# EchidnaBlack_0.net
KiCad netlist of a schematic drawn in EAGLE
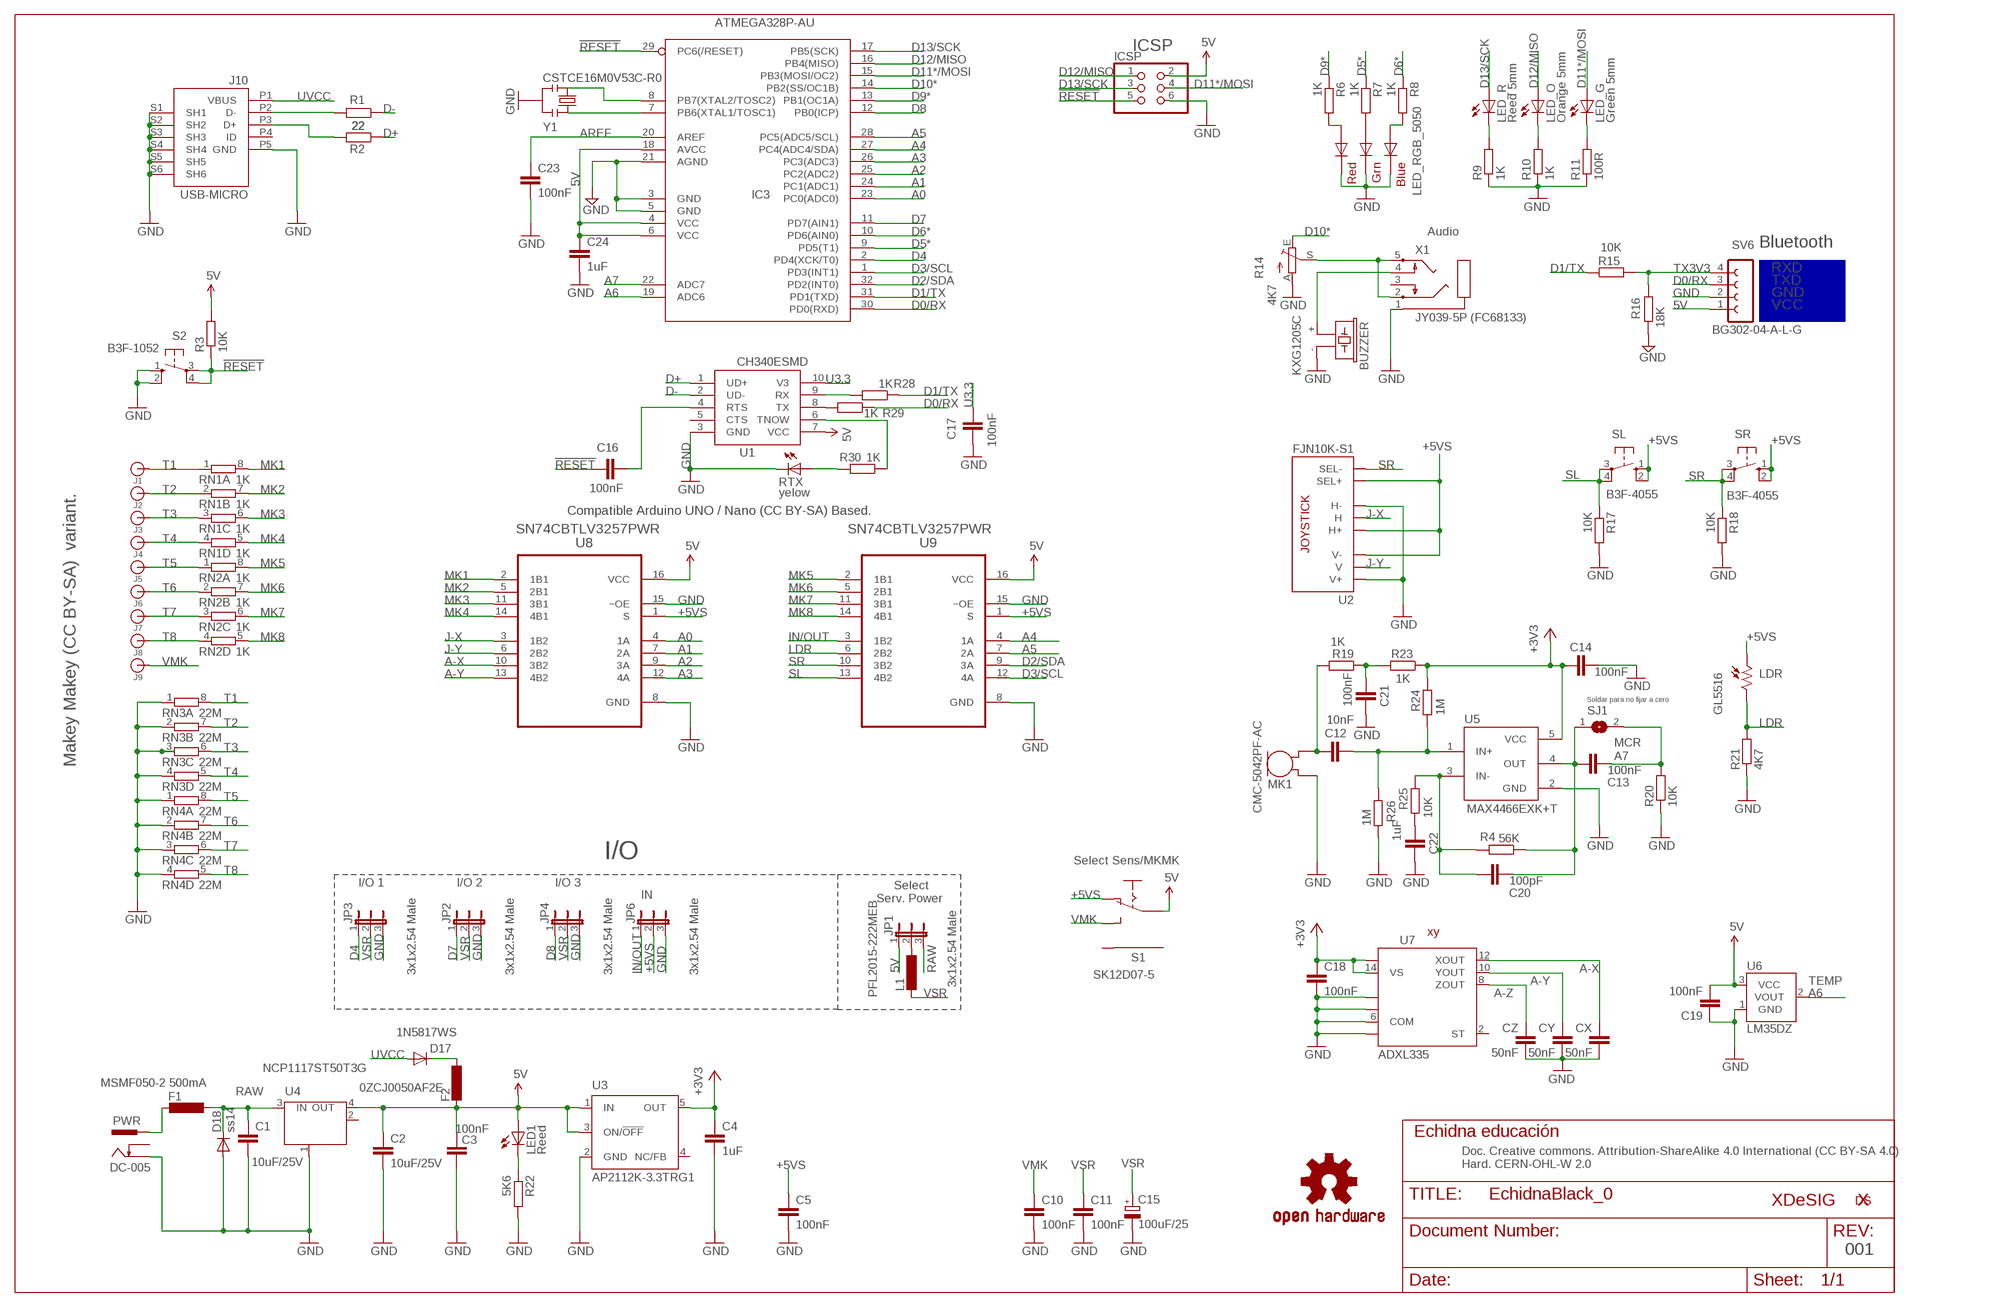
[diagram p0: schematic, sheet 1]

(export (version "E")
  (design (tool "Eeschema 10.0.6"))
  (components
    (comp (ref "BUZZER")
      (value "KXG1205C")
      (footprint "eagle-import:F_CM12P")
      (libsource (lib "eagle-import") (part "F/CM12P"))
    )
    (comp (ref "C1")
      (value "10uF/25V")
      (footprint "eagle-import:C1210")
      (libsource (lib "eagle-import") (part "C-EUC1210"))
    )
    (comp (ref "C2")
      (value "10uF/25V")
      (footprint "eagle-import:C1210")
      (libsource (lib "eagle-import") (part "C-EUC1210"))
    )
    (comp (ref "C3")
      (value "100nF")
      (footprint "eagle-import:0603-CAP")
      (libsource (lib "eagle-import") (part "CAP0603-CAP"))
    )
    (comp (ref "C4")
      (value "1uF")
      (footprint "eagle-import:0603-CAP")
      (libsource (lib "eagle-import") (part "CAP0603-CAP"))
    )
    (comp (ref "C5")
      (value "100nF")
      (footprint "eagle-import:C0603K")
      (libsource (lib "eagle-import") (part "C-EUC0603K"))
    )
    (comp (ref "C10")
      (value "100nF")
      (footprint "eagle-import:C0603K")
      (libsource (lib "eagle-import") (part "C-EUC0603K"))
    )
    (comp (ref "C11")
      (value "100nF")
      (footprint "eagle-import:C0603K")
      (libsource (lib "eagle-import") (part "C-EUC0603K"))
    )
    (comp (ref "C12")
      (value "10nF")
      (footprint "eagle-import:C0603K")
      (libsource (lib "eagle-import") (part "C-EUC0603K"))
    )
    (comp (ref "C13")
      (value "100nF")
      (footprint "eagle-import:C0603K")
      (libsource (lib "eagle-import") (part "C-EUC0603K"))
    )
    (comp (ref "C14")
      (value "100nF")
      (footprint "eagle-import:C0603K")
      (libsource (lib "eagle-import") (part "C-EUC0603K"))
    )
    (comp (ref "C15")
      (value "100uF/25")
      (footprint "eagle-import:PANASONIC_D")
      (libsource (lib "eagle-import") (part "CPOL-EUD"))
    )
    (comp (ref "C16")
      (value "100nF")
      (footprint "eagle-import:C0603-ROUND")
      (fields (field (name "PART_NUMBER") "cl10b104kbnc"))
      (libsource (lib "eagle-import") (part "0015_100NF_0603"))
    )
    (comp (ref "C17")
      (value "100nF")
      (footprint "eagle-import:C0603-ROUND")
      (fields (field (name "PART_NUMBER") "cl10b104kbnc"))
      (libsource (lib "eagle-import") (part "0015_100NF_0603"))
    )
    (comp (ref "C18")
      (value "100nF")
      (footprint "eagle-import:C0603K")
      (libsource (lib "eagle-import") (part "C-EUC0603K"))
    )
    (comp (ref "C19")
      (value "100nF")
      (footprint "eagle-import:C0603K")
      (libsource (lib "eagle-import") (part "C-EUC0603K"))
    )
    (comp (ref "C20")
      (value "100pF")
      (footprint "eagle-import:C0603K")
      (libsource (lib "eagle-import") (part "C-EUC0603K"))
    )
    (comp (ref "C21")
      (value "100nF")
      (footprint "eagle-import:C0603K")
      (libsource (lib "eagle-import") (part "C-EUC0603K"))
    )
    (comp (ref "C22")
      (value "1uF")
      (footprint "eagle-import:C0603K")
      (libsource (lib "eagle-import") (part "C-EUC0603K"))
    )
    (comp (ref "C23")
      (value "100nF")
      (footprint "eagle-import:C0603-ROUND")
      (fields (field (name "PART_NUMBER") "cl10b104kbnc"))
      (libsource (lib "eagle-import") (part "0015_100NF_0603"))
    )
    (comp (ref "C24")
      (value "1uF")
      (footprint "eagle-import:C0603-ROUND")
      (fields (field (name "PART_NUMBER") "1uF_0603/GRM188R61E105KA12D"))
      (libsource (lib "eagle-import") (part "0006_1UF_0603/GRM188R61E105KA12D"))
    )
    (comp (ref "CX")
      (value "50nF")
      (footprint "eagle-import:C0603K")
      (libsource (lib "eagle-import") (part "C-EUC0603K"))
    )
    (comp (ref "CY")
      (value "50nF")
      (footprint "eagle-import:C0603K")
      (libsource (lib "eagle-import") (part "C-EUC0603K"))
    )
    (comp (ref "CZ")
      (value "50nF")
      (footprint "eagle-import:C0603K")
      (libsource (lib "eagle-import") (part "C-EUC0603K"))
    )
    (comp (ref "D17")
      (value "1N5817WS")
      (footprint "eagle-import:SOD-323")
      (libsource (lib "eagle-import") (part "DIODESOD"))
    )
    (comp (ref "D18")
      (value "ss14")
      (footprint "eagle-import:DO214AC")
      (libsource (lib "eagle-import") (part "DIODE-DO214AC"))
    )
    (comp (ref "F1")
      (value "MSMF050-2 500mA")
      (footprint "eagle-import:L1812")
      (libsource (lib "eagle-import") (part "L-EUL1812"))
    )
    (comp (ref "F2")
      (value "0ZCJ0050AF2E")
      (footprint "eagle-import:L3216C")
      (libsource (lib "eagle-import") (part "L-EUL3216C"))
    )
    (comp (ref "IC3")
      (value "ATMEGA328P-AU")
      (footprint "eagle-import:TQFP32-08")
      (libsource (lib "eagle-import") (part "0265_ATMEGA328P-AU"))
    )
    (comp (ref "ICSP")
      (value "0114_PH254-203DF118A00V")
      (footprint "eagle-import:2X03")
      (fields (field (name "PART_NUMBER") "PH254-203DF118A00V"))
      (libsource (lib "eagle-import") (part "0114_PH254-203DF118A00V"))
    )
    (comp (ref "J1")
      (value "Hole")
      (footprint "eagle-import:BANANA_CONN")
      (libsource (lib "eagle-import") (part "BANANA_CONN"))
    )
    (comp (ref "J2")
      (value "Hole")
      (footprint "eagle-import:BANANA_CONN")
      (libsource (lib "eagle-import") (part "BANANA_CONN"))
    )
    (comp (ref "J3")
      (value "Hole")
      (footprint "eagle-import:BANANA_CONN")
      (libsource (lib "eagle-import") (part "BANANA_CONN"))
    )
    (comp (ref "J4")
      (value "Hole")
      (footprint "eagle-import:BANANA_CONN")
      (libsource (lib "eagle-import") (part "BANANA_CONN"))
    )
    (comp (ref "J5")
      (value "Hole")
      (footprint "eagle-import:BANANA_CONN")
      (libsource (lib "eagle-import") (part "BANANA_CONN"))
    )
    (comp (ref "J6")
      (value "Hole")
      (footprint "eagle-import:BANANA_CONN")
      (libsource (lib "eagle-import") (part "BANANA_CONN"))
    )
    (comp (ref "J7")
      (value "Hole")
      (footprint "eagle-import:BANANA_CONN")
      (libsource (lib "eagle-import") (part "BANANA_CONN"))
    )
    (comp (ref "J8")
      (value "Hole")
      (footprint "eagle-import:BANANA_CONN")
      (libsource (lib "eagle-import") (part "BANANA_CONN"))
    )
    (comp (ref "J9")
      (value "Hole")
      (footprint "eagle-import:BANANA_CONN")
      (libsource (lib "eagle-import") (part "BANANA_CONN"))
    )
    (comp (ref "J10")
      (value "USB-MICRO")
      (footprint "eagle-import:SMARTPRJ_CON2_USB_MICRO_B_AT")
      (libsource (lib "eagle-import") (part "SMARTPRJ_MYCON2_USB-MINI-B"))
    )
    (comp (ref "JP1")
      (value "3x1x2.54 Male")
      (footprint "eagle-import:JUMPER_JP2")
      (libsource (lib "eagle-import") (part "JUMPER_JP2E"))
    )
    (comp (ref "JP2")
      (value "3x1x2.54 Male")
      (footprint "eagle-import:JUMPER_JP2")
      (libsource (lib "eagle-import") (part "JUMPER_JP2E"))
    )
    (comp (ref "JP3")
      (value "3x1x2.54 Male")
      (footprint "eagle-import:JUMPER_JP2")
      (libsource (lib "eagle-import") (part "JUMPER_JP2E"))
    )
    (comp (ref "JP4")
      (value "3x1x2.54 Male")
      (footprint "eagle-import:JUMPER_JP2")
      (libsource (lib "eagle-import") (part "JUMPER_JP2E"))
    )
    (comp (ref "JP6")
      (value "3x1x2.54 Male")
      (footprint "eagle-import:JUMPER_JP2")
      (libsource (lib "eagle-import") (part "JUMPER_JP2E"))
    )
    (comp (ref "L1")
      (value "PFL2015-222MEB")
      (footprint "eagle-import:L3216C")
      (libsource (lib "eagle-import") (part "L-EUL3216C"))
    )
    (comp (ref "LDR")
      (value "GL5516")
      (footprint "eagle-import:T0-46-A10XX")
      (libsource (lib "eagle-import") (part "A1060_34"))
    )
    (comp (ref "LED1")
      (value "Reed")
      (footprint "eagle-import:CHIPLED_0603")
      (libsource (lib "eagle-import") (part "led_LEDCHIPLED_0603"))
    )
    (comp (ref "LED_G")
      (value "Green 5mm")
      (footprint "eagle-import:LED5MM")
      (libsource (lib "eagle-import") (part "led_LED5MM"))
    )
    (comp (ref "LED_O")
      (value "Orange 5mm")
      (footprint "eagle-import:LED5MM")
      (libsource (lib "eagle-import") (part "led_LED5MM"))
    )
    (comp (ref "LED_R")
      (value "Reed 5mm")
      (footprint "eagle-import:LED5MM")
      (libsource (lib "eagle-import") (part "led_LED5MM"))
    )
    (comp (ref "LED_RGB_5050")
      (value "CPL6C-FKBN")
      (footprint "eagle-import:PLCC6")
      (libsource (lib "eagle-import") (part "CPL6C-FKBN"))
    )
    (comp (ref "LOGO1")
      (value "SPARKFUN-AESTHETICS_OSHW-LOGOL")
      (footprint "eagle-import:SPARKFUN-AESTHETICS_OSHW-LOGO-L")
      (libsource (lib "eagle-import") (part "SPARKFUN-AESTHETICS_OSHW-LOGOL"))
    )
    (comp (ref "MK1")
      (value "CMC-5042PF-AC")
      (footprint "eagle-import:CUI_CMC-5042PF-AC")
      (fields (field (name "MF") "CUI Inc."))
      (libsource (lib "eagle-import") (part "CMC-5042PF-AC"))
    )
    (comp (ref "PWR")
      (value "DC-005")
      (footprint "eagle-import:PWR_JACK_UNI_MILLING")
      (libsource (lib "eagle-import") (part "PWR-JAKPWR_JACK_UNI_MILLING"))
    )
    (comp (ref "R1")
      (value "22")
      (footprint "eagle-import:RCL_R0603")
      (libsource (lib "eagle-import") (part "RCL_R-EU_R0603"))
    )
    (comp (ref "R2")
      (value "22")
      (footprint "eagle-import:RCL_R0603")
      (libsource (lib "eagle-import") (part "RCL_R-EU_R0603"))
    )
    (comp (ref "R3")
      (value "10K")
      (footprint "eagle-import:RCL_R0603")
      (libsource (lib "eagle-import") (part "RCL_R-EU_R0603"))
    )
    (comp (ref "R4")
      (value "56K")
      (footprint "eagle-import:RCL_R0603")
      (libsource (lib "eagle-import") (part "RCL_R-EU_R0603"))
    )
    (comp (ref "R6")
      (value "1K")
      (footprint "eagle-import:RCL_R0603")
      (libsource (lib "eagle-import") (part "RCL_R-EU_R0603"))
    )
    (comp (ref "R7")
      (value "1K")
      (footprint "eagle-import:RCL_R0603")
      (libsource (lib "eagle-import") (part "RCL_R-EU_R0603"))
    )
    (comp (ref "R8")
      (value "1K")
      (footprint "eagle-import:RCL_R0603")
      (libsource (lib "eagle-import") (part "RCL_R-EU_R0603"))
    )
    (comp (ref "R9")
      (value "1K")
      (footprint "eagle-import:RCL_R0603")
      (libsource (lib "eagle-import") (part "RCL_R-EU_R0603"))
    )
    (comp (ref "R10")
      (value "1K")
      (footprint "eagle-import:RCL_R0603")
      (libsource (lib "eagle-import") (part "RCL_R-EU_R0603"))
    )
    (comp (ref "R11")
      (value "100R")
      (footprint "eagle-import:RCL_R0603")
      (libsource (lib "eagle-import") (part "RCL_R-EU_R0603"))
    )
    (comp (ref "R14")
      (value "4K7")
      (footprint "eagle-import:CA9V")
      (libsource (lib "eagle-import") (part "TRIM_EU-CA9V"))
    )
    (comp (ref "R15")
      (value "10K")
      (footprint "eagle-import:R0603")
      (libsource (lib "eagle-import") (part "R-EU_R0603"))
    )
    (comp (ref "R16")
      (value "18K")
      (footprint "eagle-import:R0603")
      (libsource (lib "eagle-import") (part "R-EU_R0603"))
    )
    (comp (ref "R17")
      (value "10K")
      (footprint "eagle-import:RCL_R0603")
      (libsource (lib "eagle-import") (part "RCL_R-EU_R0603"))
    )
    (comp (ref "R18")
      (value "10K")
      (footprint "eagle-import:RCL_R0603")
      (libsource (lib "eagle-import") (part "RCL_R-EU_R0603"))
    )
    (comp (ref "R19")
      (value "1K")
      (footprint "eagle-import:RCL_R0603")
      (libsource (lib "eagle-import") (part "RCL_R-EU_R0603"))
    )
    (comp (ref "R20")
      (value "10K")
      (footprint "eagle-import:RCL_R0603")
      (libsource (lib "eagle-import") (part "RCL_R-EU_R0603"))
    )
    (comp (ref "R21")
      (value "4K7")
      (footprint "eagle-import:RCL_R0603")
      (libsource (lib "eagle-import") (part "RCL_R-EU_R0603"))
    )
    (comp (ref "R22")
      (value "5K6")
      (footprint "eagle-import:RCL_R0603")
      (libsource (lib "eagle-import") (part "RCL_R-EU_R0603"))
    )
    (comp (ref "R23")
      (value "1K")
      (footprint "eagle-import:RCL_R0603")
      (libsource (lib "eagle-import") (part "RCL_R-EU_R0603"))
    )
    (comp (ref "R24")
      (value "1M")
      (footprint "eagle-import:RCL_R0603")
      (libsource (lib "eagle-import") (part "RCL_R-EU_R0603"))
    )
    (comp (ref "R25")
      (value "10K")
      (footprint "eagle-import:RCL_R0603")
      (libsource (lib "eagle-import") (part "RCL_R-EU_R0603"))
    )
    (comp (ref "R26")
      (value "1M")
      (footprint "eagle-import:RCL_R0603")
      (libsource (lib "eagle-import") (part "RCL_R-EU_R0603"))
    )
    (comp (ref "R28")
      (value "1K")
      (footprint "eagle-import:R0603")
      (libsource (lib "eagle-import") (part "R-EU_R0603"))
    )
    (comp (ref "R29")
      (value "1K")
      (footprint "eagle-import:R0603")
      (libsource (lib "eagle-import") (part "R-EU_R0603"))
    )
    (comp (ref "R30")
      (value "1K")
      (footprint "eagle-import:R0603")
      (libsource (lib "eagle-import") (part "R-EU_R0603"))
    )
    (comp (ref "RN1")
      (value "1K")
      (footprint "eagle-import:RESISTOR-DIL_0603-ARC")
      (libsource (lib "eagle-import") (part "RESISTOR-DIL_4R-N0603-ARC"))
    )
    (comp (ref "RN2")
      (value "1K")
      (footprint "eagle-import:RESISTOR-DIL_0603-ARC")
      (libsource (lib "eagle-import") (part "RESISTOR-DIL_4R-N0603-ARC"))
    )
    (comp (ref "RN3")
      (value "22M")
      (footprint "eagle-import:RESISTOR-DIL_0603-ARC")
      (libsource (lib "eagle-import") (part "RESISTOR-DIL_4R-N0603-ARC"))
    )
    (comp (ref "RN4")
      (value "22M")
      (footprint "eagle-import:RESISTOR-DIL_0603-ARC")
      (libsource (lib "eagle-import") (part "RESISTOR-DIL_4R-N0603-ARC"))
    )
    (comp (ref "RTX")
      (value "yelow")
      (footprint "eagle-import:CHIPLED_0603")
      (libsource (lib "eagle-import") (part "LEDCHIPLED_0603"))
    )
    (comp (ref "S1")
      (value "SK12D07-5")
      (footprint "eagle-import:ESCORNA_SK-12D07")
      (libsource (lib "eagle-import") (part "ESCORNA_SK12F14D"))
    )
    (comp (ref "S2")
      (value "B3F-1052")
      (footprint "eagle-import:SWITCH-OMRON_B3F-10XX")
      (fields (field (name "MPN") "B3F-1000"))
      (libsource (lib "eagle-import") (part "SWITCH-OMRON_10-XX"))
    )
    (comp (ref "SJ1")
      (value "JUMPER_SJ")
      (footprint "eagle-import:JUMPER_SJ")
      (libsource (lib "eagle-import") (part "JUMPER_SJ"))
    )
    (comp (ref "SL")
      (value "B3F-4055")
      (footprint "eagle-import:B3F-40XX")
      (fields (field (name "MF") "OMRON COMPONENTS USA") (field (name "MPN") "B3F-4000"))
      (libsource (lib "eagle-import") (part "40-XX"))
    )
    (comp (ref "SR")
      (value "B3F-4055")
      (footprint "eagle-import:B3F-40XX")
      (fields (field (name "MF") "OMRON COMPONENTS USA") (field (name "MPN") "B3F-4000"))
      (libsource (lib "eagle-import") (part "40-XX"))
    )
    (comp (ref "SV6")
      (value "BG302-04-A-L-G")
      (footprint "eagle-import:FE04W")
      (libsource (lib "eagle-import") (part "FE04W"))
    )
    (comp (ref "U$2") (value "XY") (footprint "eagle-import:XY") (libsource (lib "eagle-import") (part "XY")))
    (comp (ref "U$5")
      (value "XDESIG21")
      (footprint "eagle-import:XDESIG")
      (libsource (lib "eagle-import") (part "XDESIG21"))
    )
    (comp (ref "U1")
      (value "CH340ESMD")
      (footprint "eagle-import:MSOP10")
      (fields (field (name "MF") "WCH") (field (name "MP") "CH340E"))
      (libsource (lib "eagle-import") (part "CH340ESMD"))
    )
    (comp (ref "U2")
      (value "FJN10K-S1")
      (footprint "eagle-import:JOYSTICK")
      (libsource (lib "eagle-import") (part "JOYSTICKPTH"))
    )
    (comp (ref "U3")
      (value "AP2112K-3.3TRG1")
      (footprint "eagle-import:SOT23-DBV")
      (libsource (lib "eagle-import") (part "LP2985-XXDBVR33"))
    )
    (comp (ref "U4")
      (value "NCP1117ST50T3G")
      (footprint "eagle-import:SOT223")
      (libsource (lib "eagle-import") (part "MC33269ST-3.3T3"))
    )
    (comp (ref "U5")
      (value "MAX4466EXK+T")
      (footprint "eagle-import:SOT65P210X100-5N")
      (fields (field (name "MF") "Maxim Integrated"))
      (libsource (lib "eagle-import") (part "MAX4466EXK+T"))
    )
    (comp (ref "U6")
      (value "LM35DZ")
      (footprint "eagle-import:TO-92-")
      (libsource (lib "eagle-import") (part "TMP36GRT-REEL7"))
    )
    (comp (ref "U7")
      (value "ADXL335")
      (footprint "eagle-import:LFCSP-16")
      (fields (field (name "MF") "Analog Devices") (field (name "MP") "ADXL335BCPZ"))
      (libsource (lib "eagle-import") (part "ADXL335"))
    )
    (comp (ref "U8")
      (value "SN74CBTLV3257PWR")
      (footprint "eagle-import:SOP65P640X120-16N")
      (fields (field (name "MF") "Texas Instruments"))
      (libsource (lib "eagle-import") (part "SN74CBTLV3257PWR"))
    )
    (comp (ref "U9")
      (value "SN74CBTLV3257PWR")
      (footprint "eagle-import:SOP65P640X120-16N")
      (fields (field (name "MF") "Texas Instruments"))
      (libsource (lib "eagle-import") (part "SN74CBTLV3257PWR"))
    )
    (comp (ref "X1")
      (value "JY039-5P (FC68133)")
      (footprint "eagle-import:STX3100")
      (libsource (lib "eagle-import") (part "STEREOJACK"))
    )
    (comp (ref "Y1")
      (value "CSTCE16M0V53C-R0")
      (footprint "eagle-import:RESONATOR")
      (fields (field (name "PART_NUMBER") "CSTCE16M0V53-R0"))
      (libsource (lib "eagle-import") (part "0011_CSTCE16M0V53-R0"))
    )
  )
  (nets
    (net (code "1") (name "+3V3") (class "Default")
      (node (ref "C14") (pin "2") (pinfunction "2_2") (pintype "passive"))
      (node (ref "C18") (pin "1") (pinfunction "1_1") (pintype "passive"))
      (node (ref "C4") (pin "1") (pinfunction "1_1") (pintype "passive"))
      (node (ref "R23") (pin "1") (pinfunction "1_1") (pintype "passive"))
      (node (ref "R24") (pin "1") (pinfunction "1_1") (pintype "passive"))
      (node (ref "U3") (pin "5") (pinfunction "OUT_5") (pintype "passive"))
      (node (ref "U5") (pin "5") (pinfunction "VCC_5") (pintype "power_in"))
      (node (ref "U7") (pin "14") (pinfunction "VS_14") (pintype "bidirectional"))
      (node (ref "U7") (pin "15") (pinfunction "VS_15") (pintype "bidirectional"))
    )
    (net (code "2") (name "/+5VS") (class "Default")
      (node (ref "C5") (pin "1") (pinfunction "1_1") (pintype "passive"))
      (node (ref "JP6") (pin "2") (pinfunction "2_2") (pintype "passive"))
      (node (ref "LDR") (pin "1") (pinfunction "1_1") (pintype "passive"))
      (node (ref "S1") (pin "P$2") (pinfunction "O_P$2") (pintype "passive"))
      (node (ref "SL") (pin "1") (pinfunction "S_1") (pintype "passive"))
      (node (ref "SL") (pin "2") (pinfunction "S1_2") (pintype "passive"))
      (node (ref "SR") (pin "1") (pinfunction "S_1") (pintype "passive"))
      (node (ref "SR") (pin "2") (pinfunction "S1_2") (pintype "passive"))
      (node (ref "U2") (pin "B1A") (pinfunction "SEL+_B1A") (pintype "bidirectional"))
      (node (ref "U2") (pin "H1") (pinfunction "H+_H1") (pintype "bidirectional"))
      (node (ref "U2") (pin "V3") (pinfunction "V-_V3") (pintype "bidirectional"))
      (node (ref "U8") (pin "1") (pinfunction "S_1") (pintype "input"))
      (node (ref "U9") (pin "1") (pinfunction "S_1") (pintype "input"))
    )
    (net (code "3") (name "/A-X") (class "Default")
      (node (ref "CX") (pin "1") (pinfunction "1_1") (pintype "passive"))
      (node (ref "U7") (pin "12") (pinfunction "XOUT_12") (pintype "bidirectional"))
      (node (ref "U8") (pin "10") (pinfunction "3B2_10") (pintype "bidirectional"))
    )
    (net (code "4") (name "/A-Y") (class "Default")
      (node (ref "CY") (pin "1") (pinfunction "1_1") (pintype "passive"))
      (node (ref "U7") (pin "10") (pinfunction "YOUT_10") (pintype "bidirectional"))
      (node (ref "U8") (pin "13") (pinfunction "4B2_13") (pintype "bidirectional"))
    )
    (net (code "5") (name "/A-Z") (class "Default")
      (node (ref "CZ") (pin "1") (pinfunction "1_1") (pintype "passive"))
      (node (ref "U7") (pin "8") (pinfunction "ZOUT_8") (pintype "bidirectional"))
    )
    (net (code "6") (name "/A0") (class "Default")
      (node (ref "IC3") (pin "23") (pinfunction "PC0(ADC0)_23") (pintype "bidirectional"))
      (node (ref "U8") (pin "4") (pinfunction "1A_4") (pintype "bidirectional"))
    )
    (net (code "7") (name "/A1") (class "Default")
      (node (ref "IC3") (pin "24") (pinfunction "PC1(ADC1)_24") (pintype "bidirectional"))
      (node (ref "U8") (pin "7") (pinfunction "2A_7") (pintype "bidirectional"))
    )
    (net (code "8") (name "/A2") (class "Default")
      (node (ref "IC3") (pin "25") (pinfunction "PC2(ADC2)_25") (pintype "bidirectional"))
      (node (ref "U8") (pin "9") (pinfunction "3A_9") (pintype "bidirectional"))
    )
    (net (code "9") (name "/A3") (class "Default")
      (node (ref "IC3") (pin "26") (pinfunction "PC3(ADC3)_26") (pintype "bidirectional"))
      (node (ref "U8") (pin "12") (pinfunction "4A_12") (pintype "bidirectional"))
    )
    (net (code "10") (name "/A4") (class "Default")
      (node (ref "IC3") (pin "27") (pinfunction "PC4(ADC4/SDA)_27") (pintype "bidirectional"))
      (node (ref "U9") (pin "4") (pinfunction "1A_4") (pintype "bidirectional"))
    )
    (net (code "11") (name "/A5") (class "Default")
      (node (ref "IC3") (pin "28") (pinfunction "PC5(ADC5/SCL)_28") (pintype "bidirectional"))
      (node (ref "U9") (pin "7") (pinfunction "2A_7") (pintype "bidirectional"))
    )
    (net (code "12") (name "/A6") (class "Default")
      (node (ref "IC3") (pin "19") (pinfunction "ADC6_19") (pintype "bidirectional"))
      (node (ref "U6") (pin "2") (pinfunction "VOUT_2") (pintype "bidirectional"))
    )
    (net (code "13") (name "/A7") (class "Default")
      (node (ref "C13") (pin "2") (pinfunction "2_2") (pintype "passive"))
      (node (ref "IC3") (pin "22") (pinfunction "ADC7_22") (pintype "bidirectional"))
      (node (ref "R20") (pin "2") (pinfunction "2_2") (pintype "passive"))
      (node (ref "SJ1") (pin "2") (pinfunction "2_2") (pintype "passive"))
    )
    (net (code "14") (name "/AREF") (class "Default")
      (node (ref "C23") (pin "1") (pinfunction "1_1") (pintype "passive"))
      (node (ref "IC3") (pin "20") (pinfunction "AREF_20") (pintype "bidirectional"))
    )
    (net (code "15") (name "/D+") (class "Default")
      (node (ref "R2") (pin "1") (pinfunction "1_1") (pintype "passive"))
      (node (ref "U1") (pin "1") (pinfunction "UD+_1") (pintype "bidirectional"))
    )
    (net (code "16") (name "/D-") (class "Default")
      (node (ref "R1") (pin "1") (pinfunction "1_1") (pintype "passive"))
      (node (ref "U1") (pin "2") (pinfunction "UD-_2") (pintype "bidirectional"))
    )
    (net (code "17") (name "/D0{slash}RX") (class "Default")
      (node (ref "IC3") (pin "30") (pinfunction "PD0(RXD)_30") (pintype "bidirectional"))
      (node (ref "R29") (pin "1") (pinfunction "1_1") (pintype "passive"))
      (node (ref "SV6") (pin "3") (pinfunction "3_3") (pintype "passive"))
    )
    (net (code "18") (name "/D1{slash}TX") (class "Default")
      (node (ref "IC3") (pin "31") (pinfunction "PD1(TXD)_31") (pintype "bidirectional"))
      (node (ref "R15") (pin "1") (pinfunction "1_1") (pintype "passive"))
      (node (ref "R28") (pin "1") (pinfunction "1_1") (pintype "passive"))
    )
    (net (code "19") (name "/D2{slash}SDA") (class "Default")
      (node (ref "IC3") (pin "32") (pinfunction "PD2(INT0)_32") (pintype "bidirectional"))
      (node (ref "U9") (pin "9") (pinfunction "3A_9") (pintype "bidirectional"))
    )
    (net (code "20") (name "/D3{slash}SCL") (class "Default")
      (node (ref "IC3") (pin "1") (pinfunction "PD3(INT1)_1") (pintype "bidirectional"))
      (node (ref "U9") (pin "12") (pinfunction "4A_12") (pintype "bidirectional"))
    )
    (net (code "21") (name "/D4") (class "Default")
      (node (ref "IC3") (pin "2") (pinfunction "PD4(XCK/T0)_2") (pintype "bidirectional"))
      (node (ref "JP3") (pin "1") (pinfunction "1_1") (pintype "passive"))
    )
    (net (code "22") (name "/D5*") (class "Default")
      (node (ref "IC3") (pin "9") (pinfunction "PD5(T1)_9") (pintype "bidirectional"))
      (node (ref "R7") (pin "1") (pinfunction "1_1") (pintype "passive"))
    )
    (net (code "23") (name "/D6*") (class "Default")
      (node (ref "IC3") (pin "10") (pinfunction "PD6(AIN0)_10") (pintype "bidirectional"))
      (node (ref "R8") (pin "1") (pinfunction "1_1") (pintype "passive"))
    )
    (net (code "24") (name "/D7") (class "Default")
      (node (ref "IC3") (pin "11") (pinfunction "PD7(AIN1)_11") (pintype "bidirectional"))
      (node (ref "JP2") (pin "1") (pinfunction "1_1") (pintype "passive"))
    )
    (net (code "25") (name "/D8") (class "Default")
      (node (ref "IC3") (pin "12") (pinfunction "PB0(ICP)_12") (pintype "bidirectional"))
      (node (ref "JP4") (pin "1") (pinfunction "1_1") (pintype "passive"))
    )
    (net (code "26") (name "/D9*") (class "Default")
      (node (ref "IC3") (pin "13") (pinfunction "PB1(OC1A)_13") (pintype "bidirectional"))
      (node (ref "R6") (pin "1") (pinfunction "1_1") (pintype "passive"))
    )
    (net (code "27") (name "/D10*") (class "Default")
      (node (ref "IC3") (pin "14") (pinfunction "PB2(SS/OC1B)_14") (pintype "bidirectional"))
      (node (ref "R14") (pin "E") (pinfunction "E_E") (pintype "passive"))
    )
    (net (code "28") (name "/D11*{slash}MOSI") (class "Default")
      (node (ref "IC3") (pin "15") (pinfunction "PB3(MOSI/OC2)_15") (pintype "bidirectional"))
      (node (ref "ICSP") (pin "4") (pinfunction "4_4") (pintype "passive"))
      (node (ref "LED_G") (pin "A") (pinfunction "A_A") (pintype "passive"))
    )
    (net (code "29") (name "/D12{slash}MISO") (class "Default")
      (node (ref "IC3") (pin "16") (pinfunction "PB4(MISO)_16") (pintype "bidirectional"))
      (node (ref "ICSP") (pin "1") (pinfunction "1_1") (pintype "passive"))
      (node (ref "LED_O") (pin "A") (pinfunction "A_A") (pintype "passive"))
    )
    (net (code "30") (name "/D13{slash}SCK") (class "Default")
      (node (ref "IC3") (pin "17") (pinfunction "PB5(SCK)_17") (pintype "bidirectional"))
      (node (ref "ICSP") (pin "3") (pinfunction "3_3") (pintype "passive"))
      (node (ref "LED_R") (pin "A") (pinfunction "A_A") (pintype "passive"))
    )
    (net (code "31") (name "/IN{slash}OUT") (class "Default")
      (node (ref "JP6") (pin "1") (pinfunction "1_1") (pintype "passive"))
      (node (ref "U9") (pin "3") (pinfunction "1B2_3") (pintype "bidirectional"))
    )
    (net (code "32") (name "/J-X") (class "Default")
      (node (ref "U2") (pin "H2") (pinfunction "H_H2") (pintype "bidirectional"))
      (node (ref "U8") (pin "3") (pinfunction "1B2_3") (pintype "bidirectional"))
    )
    (net (code "33") (name "/J-Y") (class "Default")
      (node (ref "U2") (pin "V2") (pinfunction "V_V2") (pintype "bidirectional"))
      (node (ref "U8") (pin "6") (pinfunction "2B2_6") (pintype "bidirectional"))
    )
    (net (code "34") (name "/LDR") (class "Default")
      (node (ref "LDR") (pin "2") (pinfunction "2_2") (pintype "passive"))
      (node (ref "R21") (pin "2") (pinfunction "2_2") (pintype "passive"))
      (node (ref "U9") (pin "6") (pinfunction "2B2_6") (pintype "bidirectional"))
    )
    (net (code "35") (name "/MK1") (class "Default")
      (node (ref "RN1") (pin "8") (pinfunction "2_8") (pintype "passive"))
      (node (ref "U8") (pin "2") (pinfunction "1B1_2") (pintype "bidirectional"))
    )
    (net (code "36") (name "/MK2") (class "Default")
      (node (ref "RN1") (pin "7") (pinfunction "2_7") (pintype "passive"))
      (node (ref "U8") (pin "5") (pinfunction "2B1_5") (pintype "bidirectional"))
    )
    (net (code "37") (name "/MK3") (class "Default")
      (node (ref "RN1") (pin "6") (pinfunction "2_6") (pintype "passive"))
      (node (ref "U8") (pin "11") (pinfunction "3B1_11") (pintype "bidirectional"))
    )
    (net (code "38") (name "/MK4") (class "Default")
      (node (ref "RN1") (pin "5") (pinfunction "2_5") (pintype "passive"))
      (node (ref "U8") (pin "14") (pinfunction "4B1_14") (pintype "bidirectional"))
    )
    (net (code "39") (name "/MK5") (class "Default")
      (node (ref "RN2") (pin "8") (pinfunction "2_8") (pintype "passive"))
      (node (ref "U9") (pin "2") (pinfunction "1B1_2") (pintype "bidirectional"))
    )
    (net (code "40") (name "/MK6") (class "Default")
      (node (ref "RN2") (pin "7") (pinfunction "2_7") (pintype "passive"))
      (node (ref "U9") (pin "5") (pinfunction "2B1_5") (pintype "bidirectional"))
    )
    (net (code "41") (name "/MK7") (class "Default")
      (node (ref "RN2") (pin "6") (pinfunction "2_6") (pintype "passive"))
      (node (ref "U9") (pin "11") (pinfunction "3B1_11") (pintype "bidirectional"))
    )
    (net (code "42") (name "/MK8") (class "Default")
      (node (ref "RN2") (pin "5") (pinfunction "2_5") (pintype "passive"))
      (node (ref "U9") (pin "14") (pinfunction "4B1_14") (pintype "bidirectional"))
    )
    (net (code "43") (name "/RAW") (class "Default")
      (node (ref "C1") (pin "1") (pinfunction "1_1") (pintype "passive"))
      (node (ref "D18") (pin "C") (pinfunction "C_C") (pintype "passive"))
      (node (ref "F1") (pin "1") (pinfunction "1_1") (pintype "passive"))
      (node (ref "JP1") (pin "3") (pinfunction "3_3") (pintype "passive"))
      (node (ref "U4") (pin "3") (pinfunction "IN_3") (pintype "input"))
    )
    (net (code "44") (name "/SL") (class "Default")
      (node (ref "R17") (pin "1") (pinfunction "1_1") (pintype "passive"))
      (node (ref "SL") (pin "3") (pinfunction "P_3") (pintype "passive"))
      (node (ref "SL") (pin "4") (pinfunction "P1_4") (pintype "passive"))
      (node (ref "U9") (pin "13") (pinfunction "4B2_13") (pintype "bidirectional"))
    )
    (net (code "45") (name "/SR") (class "Default")
      (node (ref "R18") (pin "1") (pinfunction "1_1") (pintype "passive"))
      (node (ref "SR") (pin "3") (pinfunction "P_3") (pintype "passive"))
      (node (ref "SR") (pin "4") (pinfunction "P1_4") (pintype "passive"))
      (node (ref "U2") (pin "B2A") (pinfunction "SEL-_B2A") (pintype "bidirectional"))
      (node (ref "U9") (pin "10") (pinfunction "3B2_10") (pintype "bidirectional"))
    )
    (net (code "46") (name "/T1") (class "Default")
      (node (ref "J1") (pin "P$1") (pinfunction "1_P$1") (pintype "passive"))
      (node (ref "RN1") (pin "1") (pinfunction "1_1") (pintype "passive"))
      (node (ref "RN3") (pin "8") (pinfunction "2_8") (pintype "passive"))
    )
    (net (code "47") (name "/T2") (class "Default")
      (node (ref "J2") (pin "P$1") (pinfunction "1_P$1") (pintype "passive"))
      (node (ref "RN1") (pin "2") (pinfunction "1_2") (pintype "passive"))
      (node (ref "RN3") (pin "7") (pinfunction "2_7") (pintype "passive"))
    )
    (net (code "48") (name "/T3") (class "Default")
      (node (ref "J3") (pin "P$1") (pinfunction "1_P$1") (pintype "passive"))
      (node (ref "RN1") (pin "3") (pinfunction "1_3") (pintype "passive"))
      (node (ref "RN3") (pin "6") (pinfunction "2_6") (pintype "passive"))
    )
    (net (code "49") (name "/T4") (class "Default")
      (node (ref "J4") (pin "P$1") (pinfunction "1_P$1") (pintype "passive"))
      (node (ref "RN1") (pin "4") (pinfunction "1_4") (pintype "passive"))
      (node (ref "RN3") (pin "5") (pinfunction "2_5") (pintype "passive"))
    )
    (net (code "50") (name "/T5") (class "Default")
      (node (ref "J5") (pin "P$1") (pinfunction "1_P$1") (pintype "passive"))
      (node (ref "RN2") (pin "1") (pinfunction "1_1") (pintype "passive"))
      (node (ref "RN4") (pin "8") (pinfunction "2_8") (pintype "passive"))
    )
    (net (code "51") (name "/T6") (class "Default")
      (node (ref "J6") (pin "P$1") (pinfunction "1_P$1") (pintype "passive"))
      (node (ref "RN2") (pin "2") (pinfunction "1_2") (pintype "passive"))
      (node (ref "RN4") (pin "7") (pinfunction "2_7") (pintype "passive"))
    )
    (net (code "52") (name "/T7") (class "Default")
      (node (ref "J7") (pin "P$1") (pinfunction "1_P$1") (pintype "passive"))
      (node (ref "RN2") (pin "3") (pinfunction "1_3") (pintype "passive"))
      (node (ref "RN4") (pin "6") (pinfunction "2_6") (pintype "passive"))
    )
    (net (code "53") (name "/T8") (class "Default")
      (node (ref "J8") (pin "P$1") (pinfunction "1_P$1") (pintype "passive"))
      (node (ref "RN2") (pin "4") (pinfunction "1_4") (pintype "passive"))
      (node (ref "RN4") (pin "5") (pinfunction "2_5") (pintype "passive"))
    )
    (net (code "54") (name "/TX3V3") (class "Default")
      (node (ref "R15") (pin "2") (pinfunction "2_2") (pintype "passive"))
      (node (ref "R16") (pin "2") (pinfunction "2_2") (pintype "passive"))
      (node (ref "SV6") (pin "4") (pinfunction "4_4") (pintype "passive"))
    )
    (net (code "55") (name "/U3,3") (class "Default")
      (node (ref "C17") (pin "2") (pinfunction "2_2") (pintype "passive"))
      (node (ref "U1") (pin "10") (pinfunction "V3_10") (pintype "power_in"))
    )
    (net (code "56") (name "/UVCC") (class "Default")
      (node (ref "D17") (pin "2") (pinfunction "A_2") (pintype "passive"))
      (node (ref "J10") (pin "P1") (pinfunction "VBUS_P1") (pintype "power_in"))
    )
    (net (code "57") (name "/VMK") (class "Default")
      (node (ref "C10") (pin "1") (pinfunction "1_1") (pintype "passive"))
      (node (ref "J9") (pin "P$1") (pinfunction "1_P$1") (pintype "passive"))
      (node (ref "S1") (pin "P$3") (pinfunction "S_P$3") (pintype "passive"))
    )
    (net (code "58") (name "/VSR") (class "Default")
      (node (ref "C11") (pin "1") (pinfunction "1_1") (pintype "passive"))
      (node (ref "C15") (pin "+") (pinfunction "+_+") (pintype "passive"))
      (node (ref "JP2") (pin "2") (pinfunction "2_2") (pintype "passive"))
      (node (ref "JP3") (pin "2") (pinfunction "2_2") (pintype "passive"))
      (node (ref "JP4") (pin "2") (pinfunction "2_2") (pintype "passive"))
      (node (ref "L1") (pin "2") (pinfunction "2_2") (pintype "passive"))
    )
    (net (code "59") (name "/~{RESET}") (class "Default")
      (node (ref "C16") (pin "1") (pinfunction "1_1") (pintype "passive"))
      (node (ref "IC3") (pin "29") (pinfunction "PC6(/RESET)_29") (pintype "bidirectional"))
      (node (ref "ICSP") (pin "5") (pinfunction "5_5") (pintype "passive"))
      (node (ref "R3") (pin "1") (pinfunction "1_1") (pintype "passive"))
      (node (ref "S2") (pin "3") (pinfunction "P_3") (pintype "passive"))
      (node (ref "S2") (pin "4") (pinfunction "P1_4") (pintype "passive"))
    )
    (net (code "60") (name "5V") (class "Default")
      (node (ref "C19") (pin "2") (pinfunction "2_2") (pintype "passive"))
      (node (ref "C2") (pin "1") (pinfunction "1_1") (pintype "passive"))
      (node (ref "C24") (pin "1") (pinfunction "1_1") (pintype "passive"))
      (node (ref "C3") (pin "2") (pinfunction "2_2") (pintype "passive"))
      (node (ref "F2") (pin "2") (pinfunction "2_2") (pintype "passive"))
      (node (ref "IC3") (pin "18") (pinfunction "AVCC_18") (pintype "bidirectional"))
      (node (ref "IC3") (pin "4") (pinfunction "VCC_4") (pintype "bidirectional"))
      (node (ref "IC3") (pin "6") (pinfunction "VCC_6") (pintype "bidirectional"))
      (node (ref "ICSP") (pin "2") (pinfunction "2_2") (pintype "passive"))
      (node (ref "JP1") (pin "1") (pinfunction "1_1") (pintype "passive"))
      (node (ref "LED1") (pin "A") (pinfunction "A_A") (pintype "passive"))
      (node (ref "R3") (pin "2") (pinfunction "2_2") (pintype "passive"))
      (node (ref "S1") (pin "P$1") (pinfunction "P_P$1") (pintype "passive"))
      (node (ref "SV6") (pin "1") (pinfunction "1_1") (pintype "passive"))
      (node (ref "U1") (pin "7") (pinfunction "VCC_7") (pintype "power_in"))
      (node (ref "U3") (pin "1") (pinfunction "IN_1") (pintype "input"))
      (node (ref "U3") (pin "3") (pinfunction "ON/~{OFF}_3") (pintype "input"))
      (node (ref "U4") (pin "4") (pinfunction "OUT_4") (pintype "passive"))
      (node (ref "U6") (pin "3") (pinfunction "VCC_3") (pintype "bidirectional"))
      (node (ref "U8") (pin "16") (pinfunction "VCC_16") (pintype "power_in"))
      (node (ref "U9") (pin "16") (pinfunction "VCC_16") (pintype "power_in"))
    )
    (net (code "61") (name "GND") (class "Default")
      (node (ref "BUZZER") (pin "-") (pinfunction "2_-") (pintype "passive"))
      (node (ref "C1") (pin "2") (pinfunction "2_2") (pintype "passive"))
      (node (ref "C10") (pin "2") (pinfunction "2_2") (pintype "passive"))
      (node (ref "C11") (pin "2") (pinfunction "2_2") (pintype "passive"))
      (node (ref "C14") (pin "1") (pinfunction "1_1") (pintype "passive"))
      (node (ref "C15") (pin "-") (pinfunction "-_-") (pintype "passive"))
      (node (ref "C17") (pin "1") (pinfunction "1_1") (pintype "passive"))
      (node (ref "C18") (pin "2") (pinfunction "2_2") (pintype "passive"))
      (node (ref "C19") (pin "1") (pinfunction "1_1") (pintype "passive"))
      (node (ref "C2") (pin "2") (pinfunction "2_2") (pintype "passive"))
      (node (ref "C21") (pin "1") (pinfunction "1_1") (pintype "passive"))
      (node (ref "C22") (pin "1") (pinfunction "1_1") (pintype "passive"))
      (node (ref "C23") (pin "2") (pinfunction "2_2") (pintype "passive"))
      (node (ref "C24") (pin "2") (pinfunction "2_2") (pintype "passive"))
      (node (ref "C3") (pin "1") (pinfunction "1_1") (pintype "passive"))
      (node (ref "C4") (pin "2") (pinfunction "2_2") (pintype "passive"))
      (node (ref "C5") (pin "2") (pinfunction "2_2") (pintype "passive"))
      (node (ref "CX") (pin "2") (pinfunction "2_2") (pintype "passive"))
      (node (ref "CY") (pin "2") (pinfunction "2_2") (pintype "passive"))
      (node (ref "CZ") (pin "2") (pinfunction "2_2") (pintype "passive"))
      (node (ref "D18") (pin "A") (pinfunction "A_A") (pintype "passive"))
      (node (ref "IC3") (pin "21") (pinfunction "AGND_21") (pintype "bidirectional"))
      (node (ref "IC3") (pin "3") (pinfunction "GND_3") (pintype "bidirectional"))
      (node (ref "IC3") (pin "5") (pinfunction "GND_5") (pintype "bidirectional"))
      (node (ref "ICSP") (pin "6") (pinfunction "6_6") (pintype "passive"))
      (node (ref "J10") (pin "P5") (pinfunction "GND_P5") (pintype "passive"))
      (node (ref "J10") (pin "S1") (pinfunction "SH1_S1") (pintype "passive"))
      (node (ref "J10") (pin "S2") (pinfunction "SH2_S2") (pintype "passive"))
      (node (ref "J10") (pin "S3") (pinfunction "SH3_S3") (pintype "passive"))
      (node (ref "J10") (pin "S4") (pinfunction "SH4_S4") (pintype "passive"))
      (node (ref "J10") (pin "S5") (pinfunction "SH5_S5") (pintype "passive"))
      (node (ref "J10") (pin "S6") (pinfunction "SH6_S6") (pintype "passive"))
      (node (ref "JP2") (pin "3") (pinfunction "3_3") (pintype "passive"))
      (node (ref "JP3") (pin "3") (pinfunction "3_3") (pintype "passive"))
      (node (ref "JP4") (pin "3") (pinfunction "3_3") (pintype "passive"))
      (node (ref "JP6") (pin "3") (pinfunction "3_3") (pintype "passive"))
      (node (ref "LED_RGB_5050") (pin "4") (pinfunction "BLUE_C_4") (pintype "bidirectional"))
      (node (ref "LED_RGB_5050") (pin "5") (pinfunction "GREEN_C_5") (pintype "bidirectional"))
      (node (ref "LED_RGB_5050") (pin "6") (pinfunction "RED_C_6") (pintype "bidirectional"))
      (node (ref "MK1") (pin "GND") (pinfunction "GND_GND") (pintype "power_in"))
      (node (ref "PWR") (pin "-") (pinfunction "-_-") (pintype "passive"))
      (node (ref "R10") (pin "1") (pinfunction "1_1") (pintype "passive"))
      (node (ref "R11") (pin "1") (pinfunction "1_1") (pintype "passive"))
      (node (ref "R14") (pin "A") (pinfunction "A_A") (pintype "passive"))
      (node (ref "R16") (pin "1") (pinfunction "1_1") (pintype "passive"))
      (node (ref "R17") (pin "2") (pinfunction "2_2") (pintype "passive"))
      (node (ref "R18") (pin "2") (pinfunction "2_2") (pintype "passive"))
      (node (ref "R20") (pin "1") (pinfunction "1_1") (pintype "passive"))
      (node (ref "R21") (pin "1") (pinfunction "1_1") (pintype "passive"))
      (node (ref "R22") (pin "2") (pinfunction "2_2") (pintype "passive"))
      (node (ref "R26") (pin "2") (pinfunction "2_2") (pintype "passive"))
      (node (ref "R9") (pin "1") (pinfunction "1_1") (pintype "passive"))
      (node (ref "RN3") (pin "1") (pinfunction "1_1") (pintype "passive"))
      (node (ref "RN3") (pin "2") (pinfunction "1_2") (pintype "passive"))
      (node (ref "RN3") (pin "3") (pinfunction "1_3") (pintype "passive"))
      (node (ref "RN3") (pin "4") (pinfunction "1_4") (pintype "passive"))
      (node (ref "RN4") (pin "1") (pinfunction "1_1") (pintype "passive"))
      (node (ref "RN4") (pin "2") (pinfunction "1_2") (pintype "passive"))
      (node (ref "RN4") (pin "3") (pinfunction "1_3") (pintype "passive"))
      (node (ref "RN4") (pin "4") (pinfunction "1_4") (pintype "passive"))
      (node (ref "RTX") (pin "C") (pinfunction "C_C") (pintype "passive"))
      (node (ref "S2") (pin "1") (pinfunction "S_1") (pintype "passive"))
      (node (ref "S2") (pin "2") (pinfunction "S1_2") (pintype "passive"))
      (node (ref "SV6") (pin "2") (pinfunction "2_2") (pintype "passive"))
      (node (ref "U1") (pin "3") (pinfunction "GND_3") (pintype "power_in"))
      (node (ref "U2") (pin "H3") (pinfunction "H-_H3") (pintype "bidirectional"))
      (node (ref "U2") (pin "V1") (pinfunction "V+_V1") (pintype "bidirectional"))
      (node (ref "U3") (pin "2") (pinfunction "GND_2") (pintype "power_in"))
      (node (ref "U4") (pin "1") (pinfunction "GND/ADJ_1") (pintype "input"))
      (node (ref "U5") (pin "2") (pinfunction "GND_2") (pintype "power_in"))
      (node (ref "U6") (pin "1") (pinfunction "GND_1") (pintype "bidirectional"))
      (node (ref "U7") (pin "3") (pinfunction "COM_3") (pintype "bidirectional"))
      (node (ref "U7") (pin "5") (pinfunction "COM_5") (pintype "bidirectional"))
      (node (ref "U7") (pin "6") (pinfunction "COM_6") (pintype "bidirectional"))
      (node (ref "U7") (pin "7") (pinfunction "COM_7") (pintype "bidirectional"))
      (node (ref "U8") (pin "15") (pinfunction "~{OE}_15") (pintype "input"))
      (node (ref "U8") (pin "8") (pinfunction "GND_8") (pintype "passive"))
      (node (ref "U9") (pin "15") (pinfunction "~{OE}_15") (pintype "input"))
      (node (ref "U9") (pin "8") (pinfunction "GND_8") (pintype "passive"))
      (node (ref "X1") (pin "1") (pinfunction "1_1") (pintype "passive"))
      (node (ref "Y1") (pin "2") (pinfunction "2_2") (pintype "passive"))
    )
    (net (code "62") (name "Net-(BUZZER-1)") (class "Default")
      (node (ref "BUZZER") (pin "+") (pinfunction "1_+") (pintype "passive"))
      (node (ref "X1") (pin "4") (pinfunction "4_4") (pintype "passive"))
    )
    (net (code "63") (name "Net-(C12-Pad1)") (class "Default")
      (node (ref "C12") (pin "1") (pinfunction "1_1") (pintype "passive"))
      (node (ref "MK1") (pin "OUT") (pinfunction "OUT_OUT") (pintype "output"))
      (node (ref "R19") (pin "2") (pinfunction "2_2") (pintype "passive"))
    )
    (net (code "64") (name "Net-(C21-Pad2)") (class "Default")
      (node (ref "C21") (pin "2") (pinfunction "2_2") (pintype "passive"))
      (node (ref "R19") (pin "1") (pinfunction "1_1") (pintype "passive"))
      (node (ref "R23") (pin "2") (pinfunction "2_2") (pintype "passive"))
    )
    (net (code "65") (name "Net-(C22-Pad2)") (class "Default")
      (node (ref "C22") (pin "2") (pinfunction "2_2") (pintype "passive"))
      (node (ref "R25") (pin "2") (pinfunction "2_2") (pintype "passive"))
    )
    (net (code "66") (name "Net-(D17-C)") (class "Default")
      (node (ref "D17") (pin "1") (pinfunction "C_1") (pintype "passive"))
      (node (ref "F2") (pin "1") (pinfunction "1_1") (pintype "passive"))
    )
    (net (code "67") (name "Net-(F1-Pad2)") (class "Default")
      (node (ref "F1") (pin "2") (pinfunction "2_2") (pintype "passive"))
      (node (ref "PWR") (pin "+") (pinfunction "+_+") (pintype "passive"))
    )
    (net (code "68") (name "Net-(IC3-PB6(XTAL1{slash}TOSC1))") (class "Default")
      (node (ref "IC3") (pin "7") (pinfunction "PB6(XTAL1/TOSC1)_7") (pintype "bidirectional"))
      (node (ref "Y1") (pin "1") (pinfunction "1_1") (pintype "passive"))
    )
    (net (code "69") (name "Net-(IC3-PB7(XTAL2{slash}TOSC2))") (class "Default")
      (node (ref "IC3") (pin "8") (pinfunction "PB7(XTAL2/TOSC2)_8") (pintype "bidirectional"))
      (node (ref "Y1") (pin "3") (pinfunction "3_3") (pintype "passive"))
    )
    (net (code "70") (name "Net-(J10-D+)") (class "Default")
      (node (ref "J10") (pin "P3") (pinfunction "D+_P3") (pintype "bidirectional"))
      (node (ref "R2") (pin "2") (pinfunction "2_2") (pintype "passive"))
    )
    (net (code "71") (name "Net-(J10-D-)") (class "Default")
      (node (ref "J10") (pin "P2") (pinfunction "D-_P2") (pintype "bidirectional"))
      (node (ref "R1") (pin "2") (pinfunction "2_2") (pintype "passive"))
    )
    (net (code "72") (name "Net-(JP1-Pad2)") (class "Default")
      (node (ref "JP1") (pin "2") (pinfunction "2_2") (pintype "passive"))
      (node (ref "L1") (pin "1") (pinfunction "1_1") (pintype "passive"))
    )
    (net (code "73") (name "Net-(LED1-PadC)") (class "Default")
      (node (ref "LED1") (pin "C") (pinfunction "C_C") (pintype "passive"))
      (node (ref "R22") (pin "1") (pinfunction "1_1") (pintype "passive"))
    )
    (net (code "74") (name "Net-(LED_G-C)") (class "Default")
      (node (ref "LED_G") (pin "K") (pinfunction "C_K") (pintype "passive"))
      (node (ref "R11") (pin "2") (pinfunction "2_2") (pintype "passive"))
    )
    (net (code "75") (name "Net-(LED_O-C)") (class "Default")
      (node (ref "LED_O") (pin "K") (pinfunction "C_K") (pintype "passive"))
      (node (ref "R10") (pin "2") (pinfunction "2_2") (pintype "passive"))
    )
    (net (code "76") (name "Net-(LED_R-C)") (class "Default")
      (node (ref "LED_R") (pin "K") (pinfunction "C_K") (pintype "passive"))
      (node (ref "R9") (pin "2") (pinfunction "2_2") (pintype "passive"))
    )
    (net (code "77") (name "Net-(LED_RGB_5050-BLUE_A)") (class "Default")
      (node (ref "LED_RGB_5050") (pin "3") (pinfunction "BLUE_A_3") (pintype "bidirectional"))
      (node (ref "R8") (pin "2") (pinfunction "2_2") (pintype "passive"))
    )
    (net (code "78") (name "Net-(LED_RGB_5050-GREEN_A)") (class "Default")
      (node (ref "LED_RGB_5050") (pin "2") (pinfunction "GREEN_A_2") (pintype "bidirectional"))
      (node (ref "R7") (pin "2") (pinfunction "2_2") (pintype "passive"))
    )
    (net (code "79") (name "Net-(LED_RGB_5050-RED_A)") (class "Default")
      (node (ref "LED_RGB_5050") (pin "1") (pinfunction "RED_A_1") (pintype "bidirectional"))
      (node (ref "R6") (pin "2") (pinfunction "2_2") (pintype "passive"))
    )
    (net (code "80") (name "Net-(R14-PadS)") (class "Default")
      (node (ref "R14") (pin "S") (pinfunction "S_S") (pintype "passive"))
      (node (ref "X1") (pin "2") (pinfunction "2_2") (pintype "passive"))
      (node (ref "X1") (pin "5") (pinfunction "5_5") (pintype "passive"))
    )
    (net (code "81") (name "Net-(R30-Pad2)") (class "Default")
      (node (ref "R30") (pin "2") (pinfunction "2_2") (pintype "passive"))
      (node (ref "RTX") (pin "A") (pinfunction "A_A") (pintype "passive"))
    )
    (net (code "82") (name "Net-(U1-RTS)") (class "Default")
      (node (ref "C16") (pin "2") (pinfunction "2_2") (pintype "passive"))
      (node (ref "U1") (pin "4") (pinfunction "RTS_4") (pintype "output"))
    )
    (net (code "83") (name "Net-(U1-RX)") (class "Default")
      (node (ref "R28") (pin "2") (pinfunction "2_2") (pintype "passive"))
      (node (ref "U1") (pin "9") (pinfunction "RX_9") (pintype "input"))
    )
    (net (code "84") (name "Net-(U1-TNOW)") (class "Default")
      (node (ref "R30") (pin "1") (pinfunction "1_1") (pintype "passive"))
      (node (ref "U1") (pin "6") (pinfunction "TNOW_6") (pintype "output"))
    )
    (net (code "85") (name "Net-(U1-TX)") (class "Default")
      (node (ref "R29") (pin "2") (pinfunction "2_2") (pintype "passive"))
      (node (ref "U1") (pin "8") (pinfunction "TX_8") (pintype "output"))
    )
    (net (code "86") (name "Net-(U5-IN+)") (class "Default")
      (node (ref "C12") (pin "2") (pinfunction "2_2") (pintype "passive"))
      (node (ref "R24") (pin "2") (pinfunction "2_2") (pintype "passive"))
      (node (ref "R26") (pin "1") (pinfunction "1_1") (pintype "passive"))
      (node (ref "U5") (pin "1") (pinfunction "IN+_1") (pintype "input"))
    )
    (net (code "87") (name "Net-(U5-IN-)") (class "Default")
      (node (ref "C20") (pin "1") (pinfunction "1_1") (pintype "passive"))
      (node (ref "R25") (pin "1") (pinfunction "1_1") (pintype "passive"))
      (node (ref "R4") (pin "2") (pinfunction "2_2") (pintype "passive"))
      (node (ref "U5") (pin "3") (pinfunction "IN-_3") (pintype "input"))
    )
    (net (code "88") (name "Net-(U5-OUT)") (class "Default")
      (node (ref "C13") (pin "1") (pinfunction "1_1") (pintype "passive"))
      (node (ref "C20") (pin "2") (pinfunction "2_2") (pintype "passive"))
      (node (ref "R4") (pin "1") (pinfunction "1_1") (pintype "passive"))
      (node (ref "SJ1") (pin "1") (pinfunction "1_1") (pintype "passive"))
      (node (ref "U5") (pin "4") (pinfunction "OUT_4") (pintype "output"))
    )
    (net (code "89") (name "unconnected-(J10-ID-PadP4)") (class "Default")
      (node (ref "J10") (pin "P4") (pinfunction "ID_P4") (pintype "bidirectional"))
    )
    (net (code "90") (name "unconnected-(PWR-Pad--)") (class "Default")
      (node (ref "PWR") (pin "--") (pinfunction "--_--") (pintype "passive"))
    )
    (net (code "91") (name "unconnected-(S1-P$1-PadP$4)") (class "Default")
      (node (ref "S1") (pin "P$4") (pinfunction "P$1_P$4") (pintype "passive"))
    )
    (net (code "92") (name "unconnected-(S1-P$2-PadP$5)") (class "Default")
      (node (ref "S1") (pin "P$5") (pinfunction "P$2_P$5") (pintype "bidirectional"))
    )
    (net (code "93") (name "unconnected-(U1-CTS-Pad5)") (class "Default")
      (node (ref "U1") (pin "5") (pinfunction "CTS_5") (pintype "input"))
    )
    (net (code "94") (name "unconnected-(U3-NC{slash}FB-Pad4)") (class "Default")
      (node (ref "U3") (pin "4") (pinfunction "NC/FB_4") (pintype "passive"))
    )
    (net (code "95") (name "unconnected-(U4-OUT-Pad2)") (class "Default")
      (node (ref "U4") (pin "2") (pinfunction "OUT_2") (pintype "passive"))
    )
    (net (code "96") (name "unconnected-(U7-ST-Pad2)") (class "Default")
      (node (ref "U7") (pin "2") (pinfunction "ST_2") (pintype "bidirectional"))
    )
    (net (code "97") (name "unconnected-(X1-Pad3)") (class "Default")
      (node (ref "X1") (pin "3") (pinfunction "3_3") (pintype "passive"))
    )
  )
)
